# iomk4.net
KiCad netlist of a schematic drawn in EAGLE
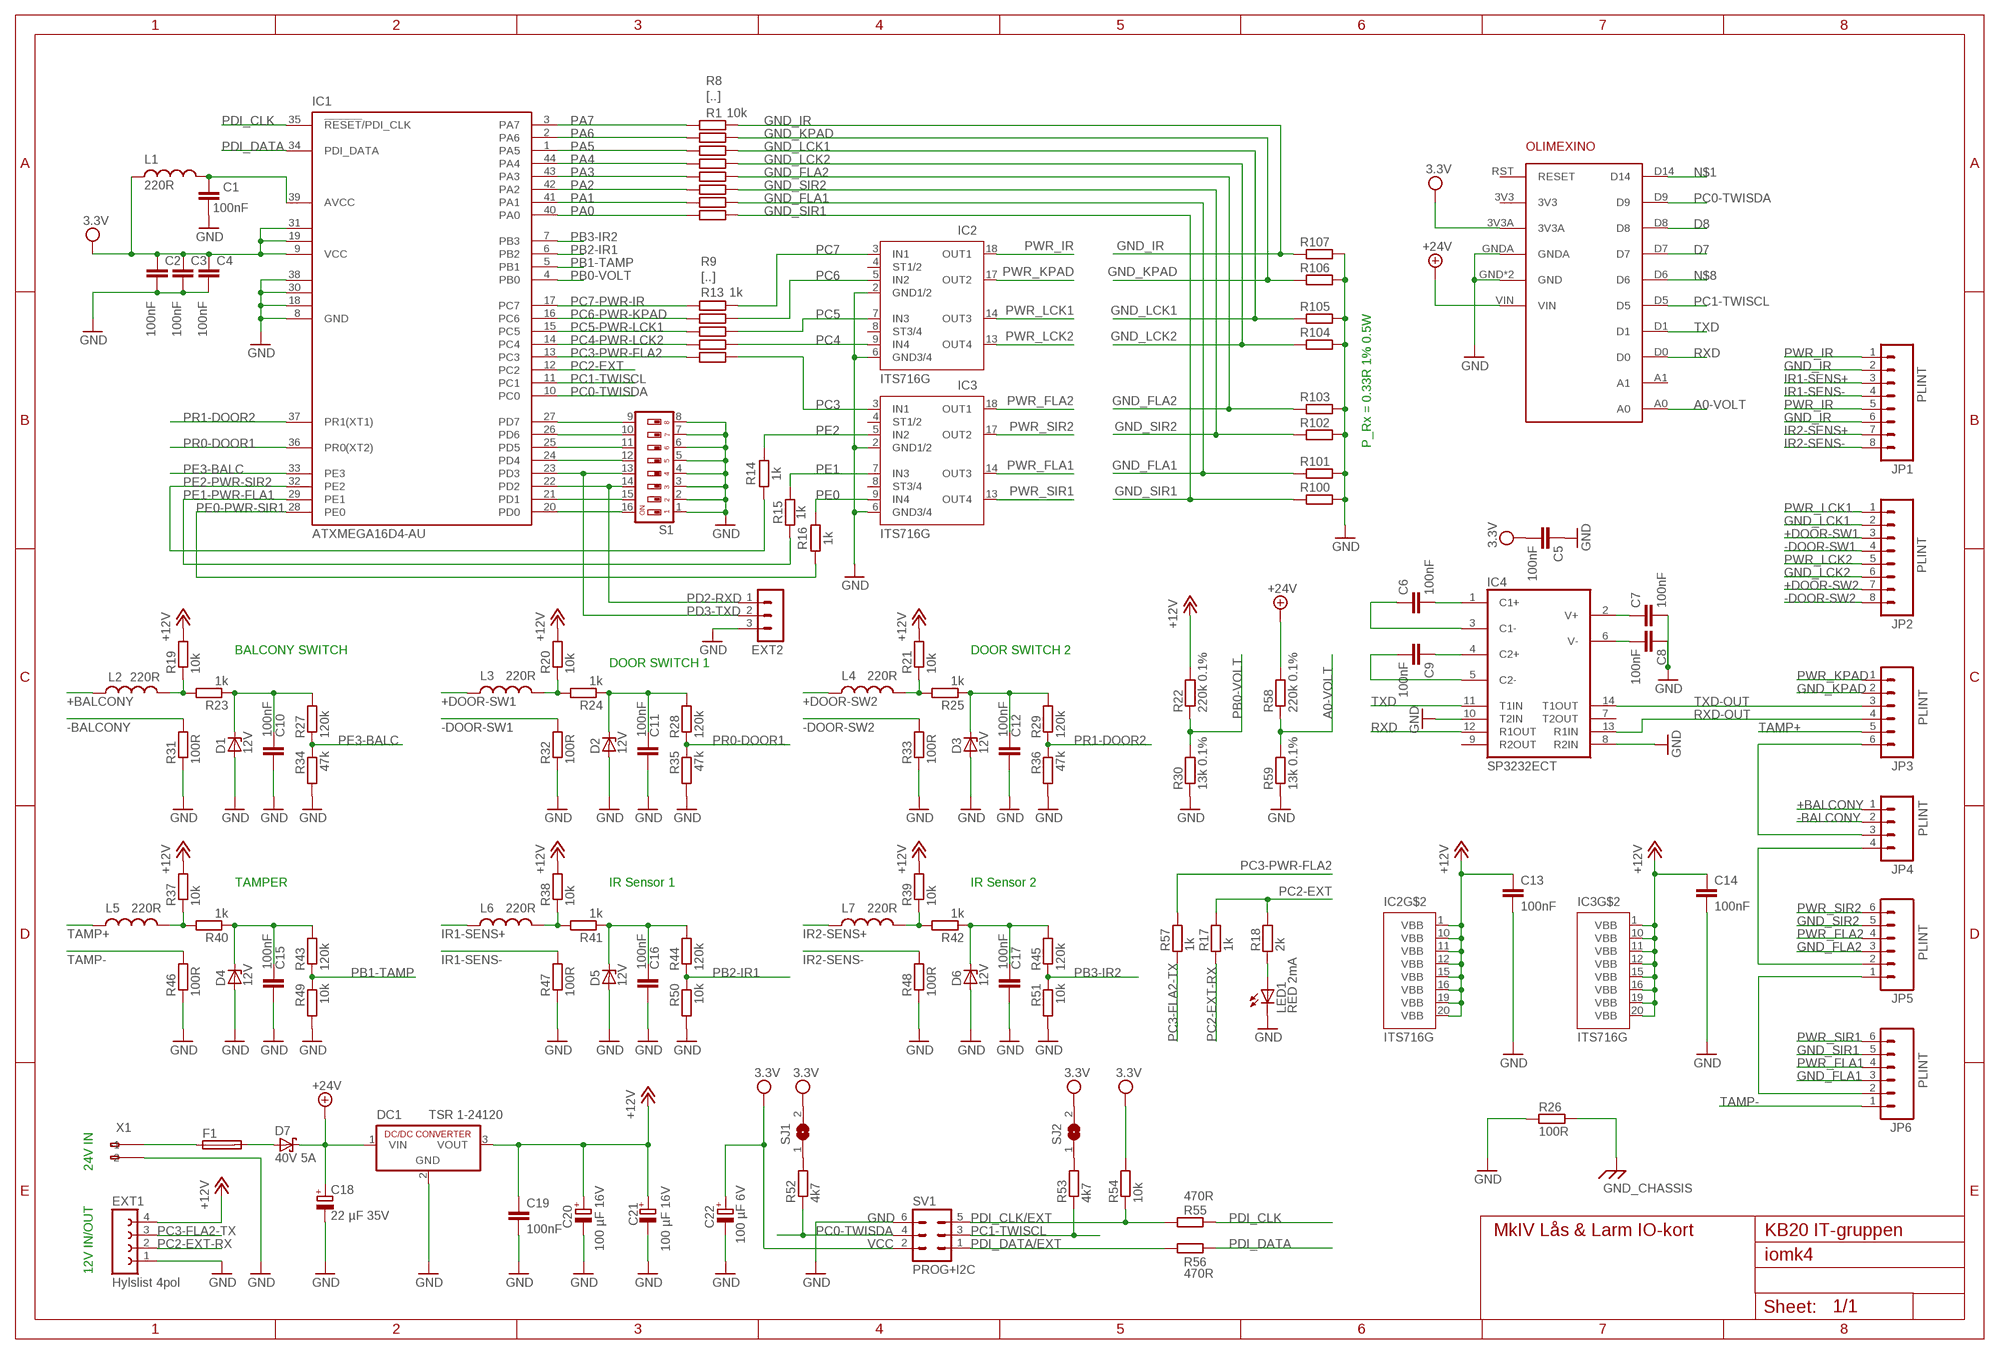
[diagram p0: schematic, sheet 1]

(export (version "E")
  (design (tool "Eeschema 10.0.6"))
  (components
    (comp (ref "C1")
      (value "100nF")
      (footprint "eagle-import:C0805")
      (libsource (lib "eagle-import") (part "CAPACITOR"))
    )
    (comp (ref "C2")
      (value "100nF")
      (footprint "eagle-import:C0805")
      (libsource (lib "eagle-import") (part "CAPACITOR"))
    )
    (comp (ref "C3")
      (value "100nF")
      (footprint "eagle-import:C0805")
      (libsource (lib "eagle-import") (part "CAPACITOR"))
    )
    (comp (ref "C4")
      (value "100nF")
      (footprint "eagle-import:C0805")
      (libsource (lib "eagle-import") (part "CAPACITOR"))
    )
    (comp (ref "C5")
      (value "100nF")
      (footprint "eagle-import:C0805")
      (libsource (lib "eagle-import") (part "CAPACITOR"))
    )
    (comp (ref "C6")
      (value "100nF")
      (footprint "eagle-import:C0805")
      (libsource (lib "eagle-import") (part "CAPACITOR"))
    )
    (comp (ref "C7")
      (value "100nF")
      (footprint "eagle-import:C0805")
      (libsource (lib "eagle-import") (part "CAPACITOR"))
    )
    (comp (ref "C8")
      (value "100nF")
      (footprint "eagle-import:C0805")
      (libsource (lib "eagle-import") (part "CAPACITOR"))
    )
    (comp (ref "C9")
      (value "100nF")
      (footprint "eagle-import:C0805")
      (libsource (lib "eagle-import") (part "CAPACITOR"))
    )
    (comp (ref "C10")
      (value "100nF")
      (footprint "eagle-import:C0805")
      (libsource (lib "eagle-import") (part "CAPACITOR"))
    )
    (comp (ref "C11")
      (value "100nF")
      (footprint "eagle-import:C0805")
      (libsource (lib "eagle-import") (part "CAPACITOR"))
    )
    (comp (ref "C12")
      (value "100nF")
      (footprint "eagle-import:C0805")
      (libsource (lib "eagle-import") (part "CAPACITOR"))
    )
    (comp (ref "C13")
      (value "100nF")
      (footprint "eagle-import:C0805")
      (libsource (lib "eagle-import") (part "CAPACITOR"))
    )
    (comp (ref "C14")
      (value "100nF")
      (footprint "eagle-import:C0805")
      (libsource (lib "eagle-import") (part "CAPACITOR"))
    )
    (comp (ref "C15")
      (value "100nF")
      (footprint "eagle-import:C0805")
      (libsource (lib "eagle-import") (part "CAPACITOR"))
    )
    (comp (ref "C16")
      (value "100nF")
      (footprint "eagle-import:C0805")
      (libsource (lib "eagle-import") (part "CAPACITOR"))
    )
    (comp (ref "C17")
      (value "100nF")
      (footprint "eagle-import:C0805")
      (libsource (lib "eagle-import") (part "CAPACITOR"))
    )
    (comp (ref "C18")
      (value "22 µF 35V")
      (footprint "eagle-import:D_7343-31R")
      (libsource (lib "eagle-import") (part "CPOL-EUD/7343-31R"))
    )
    (comp (ref "C19")
      (value "100nF")
      (footprint "eagle-import:C0805")
      (libsource (lib "eagle-import") (part "CAPACITOR"))
    )
    (comp (ref "C20")
      (value "100 µF 16V")
      (footprint "eagle-import:D_7343-31R")
      (libsource (lib "eagle-import") (part "CPOL-EUD/7343-31R"))
    )
    (comp (ref "C21")
      (value "100 µF 16V")
      (footprint "eagle-import:D_7343-31R")
      (libsource (lib "eagle-import") (part "CPOL-EUD/7343-31R"))
    )
    (comp (ref "C22")
      (value "100 µF 6V")
      (footprint "eagle-import:CT6032")
      (libsource (lib "eagle-import") (part "CPOL-EUCT6032"))
    )
    (comp (ref "D1")
      (value "12V")
      (footprint "eagle-import:SOD80C")
      (libsource (lib "eagle-import") (part "ZENER-DIODESOD80C"))
    )
    (comp (ref "D2")
      (value "12V")
      (footprint "eagle-import:SOD80C")
      (libsource (lib "eagle-import") (part "ZENER-DIODESOD80C"))
    )
    (comp (ref "D3")
      (value "12V")
      (footprint "eagle-import:SOD80C")
      (libsource (lib "eagle-import") (part "ZENER-DIODESOD80C"))
    )
    (comp (ref "D4")
      (value "12V")
      (footprint "eagle-import:SOD80C")
      (libsource (lib "eagle-import") (part "ZENER-DIODESOD80C"))
    )
    (comp (ref "D5")
      (value "12V")
      (footprint "eagle-import:SOD80C")
      (libsource (lib "eagle-import") (part "ZENER-DIODESOD80C"))
    )
    (comp (ref "D6")
      (value "12V")
      (footprint "eagle-import:SOD80C")
      (libsource (lib "eagle-import") (part "ZENER-DIODESOD80C"))
    )
    (comp (ref "D7")
      (value "40V 5A")
      (footprint "eagle-import:SMB")
      (libsource (lib "eagle-import") (part "SCHOTTKY-DIODESMD"))
    )
    (comp (ref "DC1")
      (value "TSR 1-24120")
      (footprint "eagle-import:SIP3")
      (libsource (lib "eagle-import") (part "R-78C-1.012"))
    )
    (comp (ref "EXT1")
      (value "Hylslist 4pol")
      (footprint "eagle-import:FE04")
      (libsource (lib "eagle-import") (part "FE04"))
    )
    (comp (ref "EXT2")
      (value "DEBUG PINS")
      (footprint "eagle-import:MA03")
      (libsource (lib "eagle-import") (part "MA03-1-"))
    )
    (comp (ref "F1")
      (value "Fuse Holder")
      (footprint "eagle-import:FTP_60")
      (libsource (lib "eagle-import") (part "FUSEFTP/60"))
    )
    (comp (ref "IC1")
      (value "ATXMEGA16D4-AU")
      (footprint "eagle-import:TQFP44")
      (fields
        (field (name "MF") "ATMEL")
        (field (name "MPN") "ATXMEGA16A4-AU")
        (field (name "OC_FARNELL") "1748552")
      )
      (libsource (lib "eagle-import") (part "XMEGA16A4A"))
    )
    (comp (ref "IC2")
      (value "ITS716G")
      (footprint "eagle-import:PG-DSO-20")
      (fields (field (name "ELFA") "71-017-02"))
      (libsource (lib "eagle-import") (part "BTS716G"))
    )
    (comp (ref "IC3")
      (value "ITS716G")
      (footprint "eagle-import:PG-DSO-20")
      (fields (field (name "ELFA") "71-017-02"))
      (libsource (lib "eagle-import") (part "BTS716G"))
    )
    (comp (ref "IC4")
      (value "SP3232ECT")
      (footprint "eagle-import:SO16L")
      (fields
        (field (name "MF") "MAXIM")
        (field (name "MPN") "MAX3232CWE+")
        (field (name "MF_1") "MAXIM INTEGRATED PRODUCTS")
        (field (name "MPN_1") "MAX3232CSE+")
      )
      (libsource (lib "eagle-import") (part "MAX3232WEC"))
    )
    (comp (ref "JP1")
      (value "PLINT")
      (footprint "eagle-import:FK-MPT-8-3,5")
      (libsource (lib "eagle-import") (part "FK-MPT-8-3.5"))
    )
    (comp (ref "JP2")
      (value "PLINT")
      (footprint "eagle-import:FK-MPT-8-3,5")
      (libsource (lib "eagle-import") (part "FK-MPT-8-3.5"))
    )
    (comp (ref "JP3")
      (value "PLINT")
      (footprint "eagle-import:FK-MPT-6-3,5")
      (libsource (lib "eagle-import") (part "FK-MPT-6-3.5"))
    )
    (comp (ref "JP4")
      (value "PLINT")
      (footprint "eagle-import:FK-MPT-4-3.5")
      (libsource (lib "eagle-import") (part "FK-MPT-4-3.5"))
    )
    (comp (ref "JP5")
      (value "PLINT")
      (footprint "eagle-import:FK-MPT-6-3,5")
      (libsource (lib "eagle-import") (part "FK-MPT-6-3.5"))
    )
    (comp (ref "JP6")
      (value "PLINT")
      (footprint "eagle-import:FK-MPT-6-3,5")
      (libsource (lib "eagle-import") (part "FK-MPT-6-3.5"))
    )
    (comp (ref "L1")
      (value "220R")
      (footprint "eagle-import:L0805")
      (libsource (lib "eagle-import") (part "FERRITE-BEADSL"))
    )
    (comp (ref "L2")
      (value "220R")
      (footprint "eagle-import:L0805")
      (libsource (lib "eagle-import") (part "FERRITE-BEADSL"))
    )
    (comp (ref "L3")
      (value "220R")
      (footprint "eagle-import:L0805")
      (libsource (lib "eagle-import") (part "FERRITE-BEADSL"))
    )
    (comp (ref "L4")
      (value "220R")
      (footprint "eagle-import:L0805")
      (libsource (lib "eagle-import") (part "FERRITE-BEADSL"))
    )
    (comp (ref "L5")
      (value "220R")
      (footprint "eagle-import:L0805")
      (libsource (lib "eagle-import") (part "FERRITE-BEADSL"))
    )
    (comp (ref "L6")
      (value "220R")
      (footprint "eagle-import:L0805")
      (libsource (lib "eagle-import") (part "FERRITE-BEADSL"))
    )
    (comp (ref "L7")
      (value "220R")
      (footprint "eagle-import:L0805")
      (libsource (lib "eagle-import") (part "FERRITE-BEADSL"))
    )
    (comp (ref "LED1")
      (value "RED 2mA")
      (footprint "eagle-import:SML0603")
      (libsource (lib "eagle-import") (part "LEDSML0603"))
    )
    (comp (ref "OLIMEXINO-STM1")
      (value "OLIMEXINO")
      (footprint "eagle-import:OLIMEXINO-STM32")
      (libsource (lib "eagle-import") (part "OLIMEXINO"))
    )
    (comp (ref "R1")
      (value "10k")
      (footprint "eagle-import:R0805")
      (libsource (lib "eagle-import") (part "RESISTORR0805"))
    )
    (comp (ref "R2")
      (value "10k")
      (footprint "eagle-import:R0805")
      (libsource (lib "eagle-import") (part "RESISTORR0805"))
    )
    (comp (ref "R3")
      (value "10k")
      (footprint "eagle-import:R0805")
      (libsource (lib "eagle-import") (part "RESISTORR0805"))
    )
    (comp (ref "R4")
      (value "10k")
      (footprint "eagle-import:R0805")
      (libsource (lib "eagle-import") (part "RESISTORR0805"))
    )
    (comp (ref "R5")
      (value "10k")
      (footprint "eagle-import:R0805")
      (libsource (lib "eagle-import") (part "RESISTORR0805"))
    )
    (comp (ref "R6")
      (value "10k")
      (footprint "eagle-import:R0805")
      (libsource (lib "eagle-import") (part "RESISTORR0805"))
    )
    (comp (ref "R7")
      (value "10k")
      (footprint "eagle-import:R0805")
      (libsource (lib "eagle-import") (part "RESISTORR0805"))
    )
    (comp (ref "R8")
      (value "10k")
      (footprint "eagle-import:R0805")
      (libsource (lib "eagle-import") (part "RESISTORR0805"))
    )
    (comp (ref "R9")
      (value "1k")
      (footprint "eagle-import:R0805")
      (libsource (lib "eagle-import") (part "RESISTORR0805"))
    )
    (comp (ref "R10")
      (value "1k")
      (footprint "eagle-import:R0805")
      (libsource (lib "eagle-import") (part "RESISTORR0805"))
    )
    (comp (ref "R11")
      (value "1k")
      (footprint "eagle-import:R0805")
      (libsource (lib "eagle-import") (part "RESISTORR0805"))
    )
    (comp (ref "R12")
      (value "1k")
      (footprint "eagle-import:R0805")
      (libsource (lib "eagle-import") (part "RESISTORR0805"))
    )
    (comp (ref "R13")
      (value "1k")
      (footprint "eagle-import:R0805")
      (libsource (lib "eagle-import") (part "RESISTORR0805"))
    )
    (comp (ref "R14")
      (value "1k")
      (footprint "eagle-import:R0805")
      (libsource (lib "eagle-import") (part "RESISTORR0805"))
    )
    (comp (ref "R15")
      (value "1k")
      (footprint "eagle-import:R0805")
      (libsource (lib "eagle-import") (part "RESISTORR0805"))
    )
    (comp (ref "R16")
      (value "1k")
      (footprint "eagle-import:R0805")
      (libsource (lib "eagle-import") (part "RESISTORR0805"))
    )
    (comp (ref "R17")
      (value "1k")
      (footprint "eagle-import:R0805")
      (libsource (lib "eagle-import") (part "RESISTORR0805"))
    )
    (comp (ref "R18")
      (value "2k")
      (footprint "eagle-import:R0805")
      (libsource (lib "eagle-import") (part "RESISTORR0805"))
    )
    (comp (ref "R19")
      (value "10k")
      (footprint "eagle-import:R0805")
      (libsource (lib "eagle-import") (part "RESISTORR0805"))
    )
    (comp (ref "R20")
      (value "10k")
      (footprint "eagle-import:R0805")
      (libsource (lib "eagle-import") (part "RESISTORR0805"))
    )
    (comp (ref "R21")
      (value "10k")
      (footprint "eagle-import:R0805")
      (libsource (lib "eagle-import") (part "RESISTORR0805"))
    )
    (comp (ref "R22")
      (value "220k 0.1%")
      (footprint "eagle-import:R0805")
      (libsource (lib "eagle-import") (part "RESISTORR0805"))
    )
    (comp (ref "R23")
      (value "1k")
      (footprint "eagle-import:R0805")
      (libsource (lib "eagle-import") (part "RESISTORR0805"))
    )
    (comp (ref "R24")
      (value "1k")
      (footprint "eagle-import:R0805")
      (libsource (lib "eagle-import") (part "RESISTORR0805"))
    )
    (comp (ref "R25")
      (value "1k")
      (footprint "eagle-import:R0805")
      (libsource (lib "eagle-import") (part "RESISTORR0805"))
    )
    (comp (ref "R26")
      (value "100R")
      (footprint "eagle-import:R0805")
      (libsource (lib "eagle-import") (part "RESISTORR0805"))
    )
    (comp (ref "R27")
      (value "120k")
      (footprint "eagle-import:R0805")
      (libsource (lib "eagle-import") (part "RESISTORR0805"))
    )
    (comp (ref "R28")
      (value "120k")
      (footprint "eagle-import:R0805")
      (libsource (lib "eagle-import") (part "RESISTORR0805"))
    )
    (comp (ref "R29")
      (value "120k")
      (footprint "eagle-import:R0805")
      (libsource (lib "eagle-import") (part "RESISTORR0805"))
    )
    (comp (ref "R30")
      (value "13k 0.1%")
      (footprint "eagle-import:R0805")
      (libsource (lib "eagle-import") (part "RESISTORR0805"))
    )
    (comp (ref "R31")
      (value "100R")
      (footprint "eagle-import:R0805")
      (libsource (lib "eagle-import") (part "RESISTORR0805"))
    )
    (comp (ref "R32")
      (value "100R")
      (footprint "eagle-import:R0805")
      (libsource (lib "eagle-import") (part "RESISTORR0805"))
    )
    (comp (ref "R33")
      (value "100R")
      (footprint "eagle-import:R0805")
      (libsource (lib "eagle-import") (part "RESISTORR0805"))
    )
    (comp (ref "R34")
      (value "47k")
      (footprint "eagle-import:R0805")
      (libsource (lib "eagle-import") (part "RESISTORR0805"))
    )
    (comp (ref "R35")
      (value "47k")
      (footprint "eagle-import:R0805")
      (libsource (lib "eagle-import") (part "RESISTORR0805"))
    )
    (comp (ref "R36")
      (value "47k")
      (footprint "eagle-import:R0805")
      (libsource (lib "eagle-import") (part "RESISTORR0805"))
    )
    (comp (ref "R37")
      (value "10k")
      (footprint "eagle-import:R0805")
      (libsource (lib "eagle-import") (part "RESISTORR0805"))
    )
    (comp (ref "R38")
      (value "10k")
      (footprint "eagle-import:R0805")
      (libsource (lib "eagle-import") (part "RESISTORR0805"))
    )
    (comp (ref "R39")
      (value "10k")
      (footprint "eagle-import:R0805")
      (libsource (lib "eagle-import") (part "RESISTORR0805"))
    )
    (comp (ref "R40")
      (value "1k")
      (footprint "eagle-import:R0805")
      (libsource (lib "eagle-import") (part "RESISTORR0805"))
    )
    (comp (ref "R41")
      (value "1k")
      (footprint "eagle-import:R0805")
      (libsource (lib "eagle-import") (part "RESISTORR0805"))
    )
    (comp (ref "R42")
      (value "1k")
      (footprint "eagle-import:R0805")
      (libsource (lib "eagle-import") (part "RESISTORR0805"))
    )
    (comp (ref "R43")
      (value "120k")
      (footprint "eagle-import:R0805")
      (libsource (lib "eagle-import") (part "RESISTORR0805"))
    )
    (comp (ref "R44")
      (value "120k")
      (footprint "eagle-import:R0805")
      (libsource (lib "eagle-import") (part "RESISTORR0805"))
    )
    (comp (ref "R45")
      (value "120k")
      (footprint "eagle-import:R0805")
      (libsource (lib "eagle-import") (part "RESISTORR0805"))
    )
    (comp (ref "R46")
      (value "100R")
      (footprint "eagle-import:R0805")
      (libsource (lib "eagle-import") (part "RESISTORR0805"))
    )
    (comp (ref "R47")
      (value "100R")
      (footprint "eagle-import:R0805")
      (libsource (lib "eagle-import") (part "RESISTORR0805"))
    )
    (comp (ref "R48")
      (value "100R")
      (footprint "eagle-import:R0805")
      (libsource (lib "eagle-import") (part "RESISTORR0805"))
    )
    (comp (ref "R49")
      (value "10k")
      (footprint "eagle-import:R0805")
      (libsource (lib "eagle-import") (part "RESISTORR0805"))
    )
    (comp (ref "R50")
      (value "10k")
      (footprint "eagle-import:R0805")
      (libsource (lib "eagle-import") (part "RESISTORR0805"))
    )
    (comp (ref "R51")
      (value "10k")
      (footprint "eagle-import:R0805")
      (libsource (lib "eagle-import") (part "RESISTORR0805"))
    )
    (comp (ref "R52")
      (value "4k7")
      (footprint "eagle-import:R0805")
      (libsource (lib "eagle-import") (part "RESISTORR0805"))
    )
    (comp (ref "R53")
      (value "4k7")
      (footprint "eagle-import:R0805")
      (libsource (lib "eagle-import") (part "RESISTORR0805"))
    )
    (comp (ref "R54")
      (value "10k")
      (footprint "eagle-import:R0805")
      (libsource (lib "eagle-import") (part "RESISTORR0805"))
    )
    (comp (ref "R55")
      (value "470R")
      (footprint "eagle-import:R0805")
      (libsource (lib "eagle-import") (part "RESISTORR0805"))
    )
    (comp (ref "R56")
      (value "470R")
      (footprint "eagle-import:R0805")
      (libsource (lib "eagle-import") (part "RESISTORR0805"))
    )
    (comp (ref "R57")
      (value "1k")
      (footprint "eagle-import:R0805")
      (libsource (lib "eagle-import") (part "RESISTORR0805"))
    )
    (comp (ref "R58")
      (value "220k 0.1%")
      (footprint "eagle-import:R0805")
      (libsource (lib "eagle-import") (part "RESISTORR0805"))
    )
    (comp (ref "R59")
      (value "13k 0.1%")
      (footprint "eagle-import:R0805")
      (libsource (lib "eagle-import") (part "RESISTORR0805"))
    )
    (comp (ref "R100")
      (value "0.33R")
      (footprint "eagle-import:R1210")
      (libsource (lib "eagle-import") (part "RESISTORR1210"))
    )
    (comp (ref "R101")
      (value "0.33R")
      (footprint "eagle-import:R1210")
      (libsource (lib "eagle-import") (part "RESISTORR1210"))
    )
    (comp (ref "R102")
      (value "0.33R")
      (footprint "eagle-import:R1210")
      (libsource (lib "eagle-import") (part "RESISTORR1210"))
    )
    (comp (ref "R103")
      (value "0.33R")
      (footprint "eagle-import:R1210")
      (libsource (lib "eagle-import") (part "RESISTORR1210"))
    )
    (comp (ref "R104")
      (value "0.33R")
      (footprint "eagle-import:R1210")
      (libsource (lib "eagle-import") (part "RESISTORR1210"))
    )
    (comp (ref "R105")
      (value "0.33R")
      (footprint "eagle-import:R1210")
      (libsource (lib "eagle-import") (part "RESISTORR1210"))
    )
    (comp (ref "R106")
      (value "0.33R")
      (footprint "eagle-import:R1210")
      (libsource (lib "eagle-import") (part "RESISTORR1210"))
    )
    (comp (ref "R107")
      (value "0.33R")
      (footprint "eagle-import:R1210")
      (libsource (lib "eagle-import") (part "RESISTORR1210"))
    )
    (comp (ref "S1")
      (value "DIP switches")
      (footprint "eagle-import:DIL08-SMD-MINI")
      (libsource (lib "eagle-import") (part "SWS008"))
    )
    (comp (ref "SJ1")
      (value "Solder jumper")
      (footprint "eagle-import:SJ")
      (libsource (lib "eagle-import") (part "SJ"))
    )
    (comp (ref "SJ2")
      (value "Solder jumper")
      (footprint "eagle-import:SJ")
      (libsource (lib "eagle-import") (part "SJ"))
    )
    (comp (ref "SV1")
      (value "PROG+I2C")
      (footprint "eagle-import:ML6L")
      (libsource (lib "eagle-import") (part "ML6L"))
    )
    (comp (ref "X1")
      (value "PLINT")
      (footprint "eagle-import:255-402-5")
      (libsource (lib "eagle-import") (part "255-402-5"))
    )
  )
  (nets
    (net (code "1") (name "+12V") (class "Default")
      (node (ref "C13") (pin "1") (pinfunction "1_1") (pintype "passive"))
      (node (ref "C14") (pin "1") (pinfunction "1_1") (pintype "passive"))
      (node (ref "C19") (pin "1") (pinfunction "1_1") (pintype "passive"))
      (node (ref "C20") (pin "+") (pinfunction "+_+") (pintype "passive"))
      (node (ref "C21") (pin "+") (pinfunction "+_+") (pintype "passive"))
      (node (ref "DC1") (pin "3") (pinfunction "VOUT_3") (pintype "passive"))
      (node (ref "EXT1") (pin "4") (pinfunction "4_4") (pintype "passive"))
      (node (ref "IC2") (pin "1") (pinfunction "VBB_1") (pintype "power_in"))
      (node (ref "IC2") (pin "10") (pinfunction "VBB_10") (pintype "power_in"))
      (node (ref "IC2") (pin "11") (pinfunction "VBB_11") (pintype "power_in"))
      (node (ref "IC2") (pin "12") (pinfunction "VBB_12") (pintype "power_in"))
      (node (ref "IC2") (pin "15") (pinfunction "VBB_15") (pintype "power_in"))
      (node (ref "IC2") (pin "16") (pinfunction "VBB_16") (pintype "power_in"))
      (node (ref "IC2") (pin "19") (pinfunction "VBB_19") (pintype "power_in"))
      (node (ref "IC2") (pin "20") (pinfunction "VBB_20") (pintype "power_in"))
      (node (ref "IC3") (pin "1") (pinfunction "VBB_1") (pintype "power_in"))
      (node (ref "IC3") (pin "10") (pinfunction "VBB_10") (pintype "power_in"))
      (node (ref "IC3") (pin "11") (pinfunction "VBB_11") (pintype "power_in"))
      (node (ref "IC3") (pin "12") (pinfunction "VBB_12") (pintype "power_in"))
      (node (ref "IC3") (pin "15") (pinfunction "VBB_15") (pintype "power_in"))
      (node (ref "IC3") (pin "16") (pinfunction "VBB_16") (pintype "power_in"))
      (node (ref "IC3") (pin "19") (pinfunction "VBB_19") (pintype "power_in"))
      (node (ref "IC3") (pin "20") (pinfunction "VBB_20") (pintype "power_in"))
      (node (ref "R19") (pin "2") (pinfunction "2_2") (pintype "passive"))
      (node (ref "R20") (pin "2") (pinfunction "2_2") (pintype "passive"))
      (node (ref "R21") (pin "2") (pinfunction "2_2") (pintype "passive"))
      (node (ref "R22") (pin "2") (pinfunction "2_2") (pintype "passive"))
      (node (ref "R37") (pin "2") (pinfunction "2_2") (pintype "passive"))
      (node (ref "R38") (pin "2") (pinfunction "2_2") (pintype "passive"))
      (node (ref "R39") (pin "2") (pinfunction "2_2") (pintype "passive"))
    )
    (net (code "2") (name "+24V") (class "Default")
      (node (ref "C18") (pin "+") (pinfunction "+_+") (pintype "passive"))
      (node (ref "D7") (pin "C") (pinfunction "C_C") (pintype "passive"))
      (node (ref "DC1") (pin "1") (pinfunction "VIN_1") (pintype "passive"))
      (node (ref "OLIMEXINO-STM1") (pin "VIN") (pinfunction "VIN_VIN") (pintype "bidirectional"))
      (node (ref "R58") (pin "2") (pinfunction "2_2") (pintype "passive"))
    )
    (net (code "3") (name "/+BALCONY") (class "Default")
      (node (ref "JP4") (pin "1") (pinfunction "1_1") (pintype "passive"))
      (node (ref "L2") (pin "1") (pinfunction "1_1") (pintype "passive"))
    )
    (net (code "4") (name "/+DOOR-SW1") (class "Default")
      (node (ref "JP2") (pin "3") (pinfunction "3_3") (pintype "passive"))
      (node (ref "L3") (pin "1") (pinfunction "1_1") (pintype "passive"))
    )
    (net (code "5") (name "/+DOOR-SW2") (class "Default")
      (node (ref "JP2") (pin "7") (pinfunction "7_7") (pintype "passive"))
      (node (ref "L4") (pin "1") (pinfunction "1_1") (pintype "passive"))
    )
    (net (code "6") (name "/-BALCONY") (class "Default")
      (node (ref "JP4") (pin "2") (pinfunction "2_2") (pintype "passive"))
      (node (ref "R31") (pin "2") (pinfunction "2_2") (pintype "passive"))
    )
    (net (code "7") (name "/-DOOR-SW1") (class "Default")
      (node (ref "JP2") (pin "4") (pinfunction "4_4") (pintype "passive"))
      (node (ref "R32") (pin "2") (pinfunction "2_2") (pintype "passive"))
    )
    (net (code "8") (name "/-DOOR-SW2") (class "Default")
      (node (ref "JP2") (pin "8") (pinfunction "8_8") (pintype "passive"))
      (node (ref "R33") (pin "2") (pinfunction "2_2") (pintype "passive"))
    )
    (net (code "9") (name "/A0-VOLT") (class "Default")
      (node (ref "OLIMEXINO-STM1") (pin "A0") (pinfunction "A0_A0") (pintype "bidirectional"))
      (node (ref "R58") (pin "1") (pinfunction "1_1") (pintype "passive"))
      (node (ref "R59") (pin "2") (pinfunction "2_2") (pintype "passive"))
    )
    (net (code "10") (name "/D7") (class "Default")
      (node (ref "OLIMEXINO-STM1") (pin "D7") (pinfunction "D7_D7") (pintype "bidirectional"))
    )
    (net (code "11") (name "/D8") (class "Default")
      (node (ref "OLIMEXINO-STM1") (pin "D8") (pinfunction "D8_D8") (pintype "bidirectional"))
    )
    (net (code "12") (name "/GND_FLA1") (class "Default")
      (node (ref "JP6") (pin "3") (pinfunction "3_3") (pintype "passive"))
      (node (ref "R101") (pin "1") (pinfunction "1_1") (pintype "passive"))
      (node (ref "R2") (pin "2") (pinfunction "2_2") (pintype "passive"))
    )
    (net (code "13") (name "/GND_FLA2") (class "Default")
      (node (ref "JP5") (pin "3") (pinfunction "3_3") (pintype "passive"))
      (node (ref "R103") (pin "1") (pinfunction "1_1") (pintype "passive"))
      (node (ref "R4") (pin "2") (pinfunction "2_2") (pintype "passive"))
    )
    (net (code "14") (name "/GND_IR") (class "Default")
      (node (ref "JP1") (pin "2") (pinfunction "2_2") (pintype "passive"))
      (node (ref "JP1") (pin "6") (pinfunction "6_6") (pintype "passive"))
      (node (ref "R107") (pin "1") (pinfunction "1_1") (pintype "passive"))
      (node (ref "R8") (pin "2") (pinfunction "2_2") (pintype "passive"))
    )
    (net (code "15") (name "/GND_KPAD") (class "Default")
      (node (ref "JP3") (pin "2") (pinfunction "2_2") (pintype "passive"))
      (node (ref "R106") (pin "1") (pinfunction "1_1") (pintype "passive"))
      (node (ref "R7") (pin "2") (pinfunction "2_2") (pintype "passive"))
    )
    (net (code "16") (name "/GND_LCK1") (class "Default")
      (node (ref "JP2") (pin "2") (pinfunction "2_2") (pintype "passive"))
      (node (ref "R105") (pin "1") (pinfunction "1_1") (pintype "passive"))
      (node (ref "R6") (pin "2") (pinfunction "2_2") (pintype "passive"))
    )
    (net (code "17") (name "/GND_LCK2") (class "Default")
      (node (ref "JP2") (pin "6") (pinfunction "6_6") (pintype "passive"))
      (node (ref "R104") (pin "1") (pinfunction "1_1") (pintype "passive"))
      (node (ref "R5") (pin "2") (pinfunction "2_2") (pintype "passive"))
    )
    (net (code "18") (name "/GND_SIR1") (class "Default")
      (node (ref "JP6") (pin "5") (pinfunction "5_5") (pintype "passive"))
      (node (ref "R1") (pin "2") (pinfunction "2_2") (pintype "passive"))
      (node (ref "R100") (pin "1") (pinfunction "1_1") (pintype "passive"))
    )
    (net (code "19") (name "/GND_SIR2") (class "Default")
      (node (ref "JP5") (pin "5") (pinfunction "5_5") (pintype "passive"))
      (node (ref "R102") (pin "1") (pinfunction "1_1") (pintype "passive"))
      (node (ref "R3") (pin "2") (pinfunction "2_2") (pintype "passive"))
    )
    (net (code "20") (name "/IR1-SENS+") (class "Default")
      (node (ref "JP1") (pin "3") (pinfunction "3_3") (pintype "passive"))
      (node (ref "L6") (pin "1") (pinfunction "1_1") (pintype "passive"))
    )
    (net (code "21") (name "/IR1-SENS-") (class "Default")
      (node (ref "JP1") (pin "4") (pinfunction "4_4") (pintype "passive"))
      (node (ref "R47") (pin "2") (pinfunction "2_2") (pintype "passive"))
    )
    (net (code "22") (name "/IR2-SENS+") (class "Default")
      (node (ref "JP1") (pin "7") (pinfunction "7_7") (pintype "passive"))
      (node (ref "L7") (pin "1") (pinfunction "1_1") (pintype "passive"))
    )
    (net (code "23") (name "/IR2-SENS-") (class "Default")
      (node (ref "JP1") (pin "8") (pinfunction "8_8") (pintype "passive"))
      (node (ref "R48") (pin "2") (pinfunction "2_2") (pintype "passive"))
    )
    (net (code "24") (name "/N$1") (class "Default")
      (node (ref "OLIMEXINO-STM1") (pin "D14") (pinfunction "D14_D14") (pintype "bidirectional"))
    )
    (net (code "25") (name "/N$8") (class "Default")
      (node (ref "OLIMEXINO-STM1") (pin "D6") (pinfunction "D6_D6") (pintype "bidirectional"))
    )
    (net (code "26") (name "/PA0") (class "Default")
      (node (ref "IC1") (pin "40") (pinfunction "PA0_40") (pintype "bidirectional"))
      (node (ref "R1") (pin "1") (pinfunction "1_1") (pintype "passive"))
    )
    (net (code "27") (name "/PA1") (class "Default")
      (node (ref "IC1") (pin "41") (pinfunction "PA1_41") (pintype "bidirectional"))
      (node (ref "R2") (pin "1") (pinfunction "1_1") (pintype "passive"))
    )
    (net (code "28") (name "/PA2") (class "Default")
      (node (ref "IC1") (pin "42") (pinfunction "PA2_42") (pintype "bidirectional"))
      (node (ref "R3") (pin "1") (pinfunction "1_1") (pintype "passive"))
    )
    (net (code "29") (name "/PA3") (class "Default")
      (node (ref "IC1") (pin "43") (pinfunction "PA3_43") (pintype "bidirectional"))
      (node (ref "R4") (pin "1") (pinfunction "1_1") (pintype "passive"))
    )
    (net (code "30") (name "/PA4") (class "Default")
      (node (ref "IC1") (pin "44") (pinfunction "PA4_44") (pintype "bidirectional"))
      (node (ref "R5") (pin "1") (pinfunction "1_1") (pintype "passive"))
    )
    (net (code "31") (name "/PA5") (class "Default")
      (node (ref "IC1") (pin "1") (pinfunction "PA5_1") (pintype "bidirectional"))
      (node (ref "R6") (pin "1") (pinfunction "1_1") (pintype "passive"))
    )
    (net (code "32") (name "/PA6") (class "Default")
      (node (ref "IC1") (pin "2") (pinfunction "PA6_2") (pintype "bidirectional"))
      (node (ref "R7") (pin "1") (pinfunction "1_1") (pintype "passive"))
    )
    (net (code "33") (name "/PA7") (class "Default")
      (node (ref "IC1") (pin "3") (pinfunction "PA7_3") (pintype "bidirectional"))
      (node (ref "R8") (pin "1") (pinfunction "1_1") (pintype "passive"))
    )
    (net (code "34") (name "/PB0-VOLT") (class "Default")
      (node (ref "IC1") (pin "4") (pinfunction "PB0_4") (pintype "bidirectional"))
      (node (ref "R22") (pin "1") (pinfunction "1_1") (pintype "passive"))
      (node (ref "R30") (pin "2") (pinfunction "2_2") (pintype "passive"))
    )
    (net (code "35") (name "/PB1-TAMP") (class "Default")
      (node (ref "IC1") (pin "5") (pinfunction "PB1_5") (pintype "bidirectional"))
      (node (ref "R43") (pin "1") (pinfunction "1_1") (pintype "passive"))
      (node (ref "R49") (pin "1") (pinfunction "1_1") (pintype "passive"))
    )
    (net (code "36") (name "/PB2-IR1") (class "Default")
      (node (ref "IC1") (pin "6") (pinfunction "PB2_6") (pintype "bidirectional"))
      (node (ref "R44") (pin "1") (pinfunction "1_1") (pintype "passive"))
      (node (ref "R50") (pin "1") (pinfunction "1_1") (pintype "passive"))
    )
    (net (code "37") (name "/PB3-IR2") (class "Default")
      (node (ref "IC1") (pin "7") (pinfunction "PB3_7") (pintype "bidirectional"))
      (node (ref "R45") (pin "1") (pinfunction "1_1") (pintype "passive"))
      (node (ref "R51") (pin "1") (pinfunction "1_1") (pintype "passive"))
    )
    (net (code "38") (name "/PC0-TWISDA") (class "Default")
      (node (ref "IC1") (pin "10") (pinfunction "PC0_10") (pintype "bidirectional"))
      (node (ref "OLIMEXINO-STM1") (pin "D9") (pinfunction "D9_D9") (pintype "bidirectional"))
      (node (ref "R52") (pin "1") (pinfunction "1_1") (pintype "passive"))
      (node (ref "SV1") (pin "4") (pinfunction "4_4") (pintype "passive"))
    )
    (net (code "39") (name "/PC1-TWISCL") (class "Default")
      (node (ref "IC1") (pin "11") (pinfunction "PC1_11") (pintype "bidirectional"))
      (node (ref "OLIMEXINO-STM1") (pin "D5") (pinfunction "D5_D5") (pintype "bidirectional"))
      (node (ref "R53") (pin "1") (pinfunction "1_1") (pintype "passive"))
      (node (ref "SV1") (pin "3") (pinfunction "3_3") (pintype "passive"))
    )
    (net (code "40") (name "/PC2-EXT") (class "Default")
      (node (ref "IC1") (pin "12") (pinfunction "PC2_12") (pintype "bidirectional"))
      (node (ref "R17") (pin "1") (pinfunction "1_1") (pintype "passive"))
      (node (ref "R18") (pin "1") (pinfunction "1_1") (pintype "passive"))
    )
    (net (code "41") (name "/PC2-EXT-RX") (class "Default")
      (node (ref "EXT1") (pin "2") (pinfunction "2_2") (pintype "passive"))
      (node (ref "R17") (pin "2") (pinfunction "2_2") (pintype "passive"))
    )
    (net (code "42") (name "/PC3") (class "Default")
      (node (ref "IC3") (pin "3") (pinfunction "IN1_3") (pintype "input"))
      (node (ref "R13") (pin "1") (pinfunction "1_1") (pintype "passive"))
    )
    (net (code "43") (name "/PC3-FLA2-TX") (class "Default")
      (node (ref "EXT1") (pin "3") (pinfunction "3_3") (pintype "passive"))
      (node (ref "R57") (pin "1") (pinfunction "1_1") (pintype "passive"))
    )
    (net (code "44") (name "/PC3-PWR-FLA2") (class "Default")
      (node (ref "IC1") (pin "13") (pinfunction "PC3_13") (pintype "bidirectional"))
      (node (ref "R13") (pin "2") (pinfunction "2_2") (pintype "passive"))
      (node (ref "R57") (pin "2") (pinfunction "2_2") (pintype "passive"))
    )
    (net (code "45") (name "/PC4") (class "Default")
      (node (ref "IC2") (pin "9") (pinfunction "IN4_9") (pintype "input"))
      (node (ref "R12") (pin "1") (pinfunction "1_1") (pintype "passive"))
    )
    (net (code "46") (name "/PC4-PWR-LCK2") (class "Default")
      (node (ref "IC1") (pin "14") (pinfunction "PC4_14") (pintype "bidirectional"))
      (node (ref "R12") (pin "2") (pinfunction "2_2") (pintype "passive"))
    )
    (net (code "47") (name "/PC5") (class "Default")
      (node (ref "IC2") (pin "7") (pinfunction "IN3_7") (pintype "input"))
      (node (ref "R11") (pin "1") (pinfunction "1_1") (pintype "passive"))
    )
    (net (code "48") (name "/PC5-PWR-LCK1") (class "Default")
      (node (ref "IC1") (pin "15") (pinfunction "PC5_15") (pintype "bidirectional"))
      (node (ref "R11") (pin "2") (pinfunction "2_2") (pintype "passive"))
    )
    (net (code "49") (name "/PC6") (class "Default")
      (node (ref "IC2") (pin "5") (pinfunction "IN2_5") (pintype "input"))
      (node (ref "R10") (pin "1") (pinfunction "1_1") (pintype "passive"))
    )
    (net (code "50") (name "/PC6-PWR-KPAD") (class "Default")
      (node (ref "IC1") (pin "16") (pinfunction "PC6_16") (pintype "bidirectional"))
      (node (ref "R10") (pin "2") (pinfunction "2_2") (pintype "passive"))
    )
    (net (code "51") (name "/PC7") (class "Default")
      (node (ref "IC2") (pin "3") (pinfunction "IN1_3") (pintype "input"))
      (node (ref "R9") (pin "1") (pinfunction "1_1") (pintype "passive"))
    )
    (net (code "52") (name "/PC7-PWR-IR") (class "Default")
      (node (ref "IC1") (pin "17") (pinfunction "PC7_17") (pintype "bidirectional"))
      (node (ref "R9") (pin "2") (pinfunction "2_2") (pintype "passive"))
    )
    (net (code "53") (name "/PD2-RXD") (class "Default")
      (node (ref "EXT2") (pin "1") (pinfunction "1_1") (pintype "passive"))
      (node (ref "IC1") (pin "22") (pinfunction "PD2_22") (pintype "bidirectional"))
      (node (ref "S1") (pin "14") (pinfunction "14_14") (pintype "passive"))
    )
    (net (code "54") (name "/PD3-TXD") (class "Default")
      (node (ref "EXT2") (pin "2") (pinfunction "2_2") (pintype "passive"))
      (node (ref "IC1") (pin "23") (pinfunction "PD3_23") (pintype "bidirectional"))
      (node (ref "S1") (pin "13") (pinfunction "13_13") (pintype "passive"))
    )
    (net (code "55") (name "/PDI_CLK") (class "Default")
      (node (ref "IC1") (pin "35") (pinfunction "~{RESET}/PDI_CLK_35") (pintype "bidirectional"))
      (node (ref "R55") (pin "1") (pinfunction "1_1") (pintype "passive"))
    )
    (net (code "56") (name "/PDI_CLK{slash}EXT") (class "Default")
      (node (ref "R54") (pin "1") (pinfunction "1_1") (pintype "passive"))
      (node (ref "R55") (pin "2") (pinfunction "2_2") (pintype "passive"))
      (node (ref "SV1") (pin "5") (pinfunction "5_5") (pintype "passive"))
    )
    (net (code "57") (name "/PDI_DATA") (class "Default")
      (node (ref "IC1") (pin "34") (pinfunction "PDI_DATA_34") (pintype "bidirectional"))
      (node (ref "R56") (pin "1") (pinfunction "1_1") (pintype "passive"))
    )
    (net (code "58") (name "/PDI_DATA{slash}EXT") (class "Default")
      (node (ref "R56") (pin "2") (pinfunction "2_2") (pintype "passive"))
      (node (ref "SV1") (pin "1") (pinfunction "1_1") (pintype "passive"))
    )
    (net (code "59") (name "/PE0") (class "Default")
      (node (ref "IC3") (pin "9") (pinfunction "IN4_9") (pintype "input"))
      (node (ref "R16") (pin "1") (pinfunction "1_1") (pintype "passive"))
    )
    (net (code "60") (name "/PE0-PWR-SIR1") (class "Default")
      (node (ref "IC1") (pin "28") (pinfunction "PE0_28") (pintype "bidirectional"))
      (node (ref "R16") (pin "2") (pinfunction "2_2") (pintype "passive"))
    )
    (net (code "61") (name "/PE1") (class "Default")
      (node (ref "IC3") (pin "7") (pinfunction "IN3_7") (pintype "input"))
      (node (ref "R15") (pin "1") (pinfunction "1_1") (pintype "passive"))
    )
    (net (code "62") (name "/PE1-PWR-FLA1") (class "Default")
      (node (ref "IC1") (pin "29") (pinfunction "PE1_29") (pintype "bidirectional"))
      (node (ref "R15") (pin "2") (pinfunction "2_2") (pintype "passive"))
    )
    (net (code "63") (name "/PE2") (class "Default")
      (node (ref "IC3") (pin "5") (pinfunction "IN2_5") (pintype "input"))
      (node (ref "R14") (pin "1") (pinfunction "1_1") (pintype "passive"))
    )
    (net (code "64") (name "/PE2-PWR-SIR2") (class "Default")
      (node (ref "IC1") (pin "32") (pinfunction "PE2_32") (pintype "bidirectional"))
      (node (ref "R14") (pin "2") (pinfunction "2_2") (pintype "passive"))
    )
    (net (code "65") (name "/PE3-BALC") (class "Default")
      (node (ref "IC1") (pin "33") (pinfunction "PE3_33") (pintype "bidirectional"))
      (node (ref "R27") (pin "1") (pinfunction "1_1") (pintype "passive"))
      (node (ref "R34") (pin "1") (pinfunction "1_1") (pintype "passive"))
    )
    (net (code "66") (name "/PR0-DOOR1") (class "Default")
      (node (ref "IC1") (pin "36") (pinfunction "PR0(XT2)_36") (pintype "bidirectional"))
      (node (ref "R28") (pin "1") (pinfunction "1_1") (pintype "passive"))
      (node (ref "R35") (pin "1") (pinfunction "1_1") (pintype "passive"))
    )
    (net (code "67") (name "/PR1-DOOR2") (class "Default")
      (node (ref "IC1") (pin "37") (pinfunction "PR1(XT1)_37") (pintype "bidirectional"))
      (node (ref "R29") (pin "1") (pinfunction "1_1") (pintype "passive"))
      (node (ref "R36") (pin "1") (pinfunction "1_1") (pintype "passive"))
    )
    (net (code "68") (name "/PWR_FLA1") (class "Default")
      (node (ref "IC3") (pin "14") (pinfunction "OUT3_14") (pintype "output"))
      (node (ref "JP6") (pin "4") (pinfunction "4_4") (pintype "passive"))
    )
    (net (code "69") (name "/PWR_FLA2") (class "Default")
      (node (ref "IC3") (pin "18") (pinfunction "OUT1_18") (pintype "output"))
      (node (ref "JP5") (pin "4") (pinfunction "4_4") (pintype "passive"))
    )
    (net (code "70") (name "/PWR_IR") (class "Default")
      (node (ref "IC2") (pin "18") (pinfunction "OUT1_18") (pintype "output"))
      (node (ref "JP1") (pin "1") (pinfunction "1_1") (pintype "passive"))
      (node (ref "JP1") (pin "5") (pinfunction "5_5") (pintype "passive"))
    )
    (net (code "71") (name "/PWR_KPAD") (class "Default")
      (node (ref "IC2") (pin "17") (pinfunction "OUT2_17") (pintype "output"))
      (node (ref "JP3") (pin "1") (pinfunction "1_1") (pintype "passive"))
    )
    (net (code "72") (name "/PWR_LCK1") (class "Default")
      (node (ref "IC2") (pin "14") (pinfunction "OUT3_14") (pintype "output"))
      (node (ref "JP2") (pin "1") (pinfunction "1_1") (pintype "passive"))
    )
    (net (code "73") (name "/PWR_LCK2") (class "Default")
      (node (ref "IC2") (pin "13") (pinfunction "OUT4_13") (pintype "output"))
      (node (ref "JP2") (pin "5") (pinfunction "5_5") (pintype "passive"))
    )
    (net (code "74") (name "/PWR_SIR1") (class "Default")
      (node (ref "IC3") (pin "13") (pinfunction "OUT4_13") (pintype "output"))
      (node (ref "JP6") (pin "6") (pinfunction "6_6") (pintype "passive"))
    )
    (net (code "75") (name "/PWR_SIR2") (class "Default")
      (node (ref "IC3") (pin "17") (pinfunction "OUT2_17") (pintype "output"))
      (node (ref "JP5") (pin "6") (pinfunction "6_6") (pintype "passive"))
    )
    (net (code "76") (name "/RXD") (class "Default")
      (node (ref "IC4") (pin "12") (pinfunction "R1OUT_12") (pintype "output"))
      (node (ref "OLIMEXINO-STM1") (pin "D0") (pinfunction "D0_D0") (pintype "bidirectional"))
    )
    (net (code "77") (name "/RXD-OUT") (class "Default")
      (node (ref "IC4") (pin "13") (pinfunction "R1IN_13") (pintype "input"))
      (node (ref "JP3") (pin "4") (pinfunction "4_4") (pintype "passive"))
    )
    (net (code "78") (name "/TAMP+") (class "Default")
      (node (ref "JP3") (pin "5") (pinfunction "5_5") (pintype "passive"))
      (node (ref "L5") (pin "1") (pinfunction "1_1") (pintype "passive"))
    )
    (net (code "79") (name "/TAMP-") (class "Default")
      (node (ref "JP6") (pin "1") (pinfunction "1_1") (pintype "passive"))
      (node (ref "R46") (pin "2") (pinfunction "2_2") (pintype "passive"))
    )
    (net (code "80") (name "/TXD") (class "Default")
      (node (ref "IC4") (pin "11") (pinfunction "T1IN_11") (pintype "input"))
      (node (ref "OLIMEXINO-STM1") (pin "D1") (pinfunction "D1_D1") (pintype "bidirectional"))
    )
    (net (code "81") (name "/TXD-OUT") (class "Default")
      (node (ref "IC4") (pin "14") (pinfunction "T1OUT_14") (pintype "output"))
      (node (ref "JP3") (pin "3") (pinfunction "3_3") (pintype "passive"))
    )
    (net (code "82") (name "3.3V") (class "Default")
      (node (ref "C2") (pin "1") (pinfunction "1_1") (pintype "passive"))
      (node (ref "C22") (pin "+") (pinfunction "+_+") (pintype "passive"))
      (node (ref "C3") (pin "1") (pinfunction "1_1") (pintype "passive"))
      (node (ref "C4") (pin "1") (pinfunction "1_1") (pintype "passive"))
      (node (ref "C5") (pin "2") (pinfunction "2_2") (pintype "passive"))
      (node (ref "IC1") (pin "19") (pinfunction "VCC1_19") (pintype "power_in"))
      (node (ref "IC1") (pin "31") (pinfunction "VCC2_31") (pintype "power_in"))
      (node (ref "IC1") (pin "9") (pinfunction "VCC_9") (pintype "power_in"))
      (node (ref "L1") (pin "1") (pinfunction "1_1") (pintype "passive"))
      (node (ref "OLIMEXINO-STM1") (pin "3V3A") (pinfunction "3V3A_3V3A") (pintype "bidirectional"))
      (node (ref "R54") (pin "2") (pinfunction "2_2") (pintype "passive"))
      (node (ref "SJ1") (pin "2") (pinfunction "2_2") (pintype "passive"))
      (node (ref "SJ2") (pin "2") (pinfunction "2_2") (pintype "passive"))
      (node (ref "SV1") (pin "2") (pinfunction "2_2") (pintype "passive"))
    )
    (net (code "83") (name "GND") (class "Default")
      (node (ref "C1") (pin "2") (pinfunction "2_2") (pintype "passive"))
      (node (ref "C10") (pin "2") (pinfunction "2_2") (pintype "passive"))
      (node (ref "C11") (pin "2") (pinfunction "2_2") (pintype "passive"))
      (node (ref "C12") (pin "2") (pinfunction "2_2") (pintype "passive"))
      (node (ref "C13") (pin "2") (pinfunction "2_2") (pintype "passive"))
      (node (ref "C14") (pin "2") (pinfunction "2_2") (pintype "passive"))
      (node (ref "C15") (pin "2") (pinfunction "2_2") (pintype "passive"))
      (node (ref "C16") (pin "2") (pinfunction "2_2") (pintype "passive"))
      (node (ref "C17") (pin "2") (pinfunction "2_2") (pintype "passive"))
      (node (ref "C18") (pin "-") (pinfunction "-_-") (pintype "passive"))
      (node (ref "C19") (pin "2") (pinfunction "2_2") (pintype "passive"))
      (node (ref "C2") (pin "2") (pinfunction "2_2") (pintype "passive"))
      (node (ref "C20") (pin "-") (pinfunction "-_-") (pintype "passive"))
      (node (ref "C21") (pin "-") (pinfunction "-_-") (pintype "passive"))
      (node (ref "C22") (pin "-") (pinfunction "-_-") (pintype "passive"))
      (node (ref "C3") (pin "2") (pinfunction "2_2") (pintype "passive"))
      (node (ref "C4") (pin "2") (pinfunction "2_2") (pintype "passive"))
      (node (ref "C5") (pin "1") (pinfunction "1_1") (pintype "passive"))
      (node (ref "C7") (pin "2") (pinfunction "2_2") (pintype "passive"))
      (node (ref "C8") (pin "1") (pinfunction "1_1") (pintype "passive"))
      (node (ref "D1") (pin "A") (pinfunction "A_A") (pintype "passive"))
      (node (ref "D2") (pin "A") (pinfunction "A_A") (pintype "passive"))
      (node (ref "D3") (pin "A") (pinfunction "A_A") (pintype "passive"))
      (node (ref "D4") (pin "A") (pinfunction "A_A") (pintype "passive"))
      (node (ref "D5") (pin "A") (pinfunction "A_A") (pintype "passive"))
      (node (ref "D6") (pin "A") (pinfunction "A_A") (pintype "passive"))
      (node (ref "DC1") (pin "2") (pinfunction "GND_2") (pintype "passive"))
      (node (ref "EXT1") (pin "1") (pinfunction "1_1") (pintype "passive"))
      (node (ref "EXT2") (pin "3") (pinfunction "3_3") (pintype "passive"))
      (node (ref "IC1") (pin "18") (pinfunction "GND1_18") (pintype "power_in"))
      (node (ref "IC1") (pin "30") (pinfunction "GND2_30") (pintype "power_in"))
      (node (ref "IC1") (pin "38") (pinfunction "GND3_38") (pintype "power_in"))
      (node (ref "IC1") (pin "8") (pinfunction "GND_8") (pintype "power_in"))
      (node (ref "IC2") (pin "2") (pinfunction "GND1/2_2") (pintype "input"))
      (node (ref "IC2") (pin "6") (pinfunction "GND3/4_6") (pintype "input"))
      (node (ref "IC3") (pin "2") (pinfunction "GND1/2_2") (pintype "input"))
      (node (ref "IC3") (pin "6") (pinfunction "GND3/4_6") (pintype "input"))
      (node (ref "IC4") (pin "10") (pinfunction "T2IN_10") (pintype "input"))
      (node (ref "IC4") (pin "8") (pinfunction "R2IN_8") (pintype "input"))
      (node (ref "LED1") (pin "C") (pinfunction "C_C") (pintype "passive"))
      (node (ref "OLIMEXINO-STM1") (pin "GND") (pinfunction "GND_GND") (pintype "bidirectional"))
      (node (ref "OLIMEXINO-STM1") (pin "GND2") (pinfunction "GND_GND2") (pintype "bidirectional"))
      (node (ref "OLIMEXINO-STM1") (pin "GNDA") (pinfunction "GNDA_GNDA") (pintype "bidirectional"))
      (node (ref "R100") (pin "2") (pinfunction "2_2") (pintype "passive"))
      (node (ref "R101") (pin "2") (pinfunction "2_2") (pintype "passive"))
      (node (ref "R102") (pin "2") (pinfunction "2_2") (pintype "passive"))
      (node (ref "R103") (pin "2") (pinfunction "2_2") (pintype "passive"))
      (node (ref "R104") (pin "2") (pinfunction "2_2") (pintype "passive"))
      (node (ref "R105") (pin "2") (pinfunction "2_2") (pintype "passive"))
      (node (ref "R106") (pin "2") (pinfunction "2_2") (pintype "passive"))
      (node (ref "R107") (pin "2") (pinfunction "2_2") (pintype "passive"))
      (node (ref "R26") (pin "2") (pinfunction "2_2") (pintype "passive"))
      (node (ref "R30") (pin "1") (pinfunction "1_1") (pintype "passive"))
      (node (ref "R31") (pin "1") (pinfunction "1_1") (pintype "passive"))
      (node (ref "R32") (pin "1") (pinfunction "1_1") (pintype "passive"))
      (node (ref "R33") (pin "1") (pinfunction "1_1") (pintype "passive"))
      (node (ref "R34") (pin "2") (pinfunction "2_2") (pintype "passive"))
      (node (ref "R35") (pin "2") (pinfunction "2_2") (pintype "passive"))
      (node (ref "R36") (pin "2") (pinfunction "2_2") (pintype "passive"))
      (node (ref "R46") (pin "1") (pinfunction "1_1") (pintype "passive"))
      (node (ref "R47") (pin "1") (pinfunction "1_1") (pintype "passive"))
      (node (ref "R48") (pin "1") (pinfunction "1_1") (pintype "passive"))
      (node (ref "R49") (pin "2") (pinfunction "2_2") (pintype "passive"))
      (node (ref "R50") (pin "2") (pinfunction "2_2") (pintype "passive"))
      (node (ref "R51") (pin "2") (pinfunction "2_2") (pintype "passive"))
      (node (ref "R59") (pin "1") (pinfunction "1_1") (pintype "passive"))
      (node (ref "S1") (pin "1") (pinfunction "1_1") (pintype "passive"))
      (node (ref "S1") (pin "2") (pinfunction "2_2") (pintype "passive"))
      (node (ref "S1") (pin "3") (pinfunction "3_3") (pintype "passive"))
      (node (ref "S1") (pin "4") (pinfunction "4_4") (pintype "passive"))
      (node (ref "S1") (pin "5") (pinfunction "5_5") (pintype "passive"))
      (node (ref "S1") (pin "6") (pinfunction "6_6") (pintype "passive"))
      (node (ref "S1") (pin "7") (pinfunction "7_7") (pintype "passive"))
      (node (ref "S1") (pin "8") (pinfunction "8_8") (pintype "passive"))
      (node (ref "SV1") (pin "6") (pinfunction "6_6") (pintype "passive"))
      (node (ref "X1") (pin "A2") (pinfunction "-2_A2") (pintype "passive"))
    )
    (net (code "84") (name "GND_CHASSIS") (class "Default")
      (node (ref "R26") (pin "1") (pinfunction "1_1") (pintype "passive"))
    )
    (net (code "85") (name "Net-(C10-Pad1)") (class "Default")
      (node (ref "C10") (pin "1") (pinfunction "1_1") (pintype "passive"))
      (node (ref "D1") (pin "C") (pinfunction "C_C") (pintype "passive"))
      (node (ref "R23") (pin "1") (pinfunction "1_1") (pintype "passive"))
      (node (ref "R27") (pin "2") (pinfunction "2_2") (pintype "passive"))
    )
    (net (code "86") (name "Net-(C11-Pad1)") (class "Default")
      (node (ref "C11") (pin "1") (pinfunction "1_1") (pintype "passive"))
      (node (ref "D2") (pin "C") (pinfunction "C_C") (pintype "passive"))
      (node (ref "R24") (pin "1") (pinfunction "1_1") (pintype "passive"))
      (node (ref "R28") (pin "2") (pinfunction "2_2") (pintype "passive"))
    )
    (net (code "87") (name "Net-(C12-Pad1)") (class "Default")
      (node (ref "C12") (pin "1") (pinfunction "1_1") (pintype "passive"))
      (node (ref "D3") (pin "C") (pinfunction "C_C") (pintype "passive"))
      (node (ref "R25") (pin "1") (pinfunction "1_1") (pintype "passive"))
      (node (ref "R29") (pin "2") (pinfunction "2_2") (pintype "passive"))
    )
    (net (code "88") (name "Net-(C15-Pad1)") (class "Default")
      (node (ref "C15") (pin "1") (pinfunction "1_1") (pintype "passive"))
      (node (ref "D4") (pin "C") (pinfunction "C_C") (pintype "passive"))
      (node (ref "R40") (pin "1") (pinfunction "1_1") (pintype "passive"))
      (node (ref "R43") (pin "2") (pinfunction "2_2") (pintype "passive"))
    )
    (net (code "89") (name "Net-(C16-Pad1)") (class "Default")
      (node (ref "C16") (pin "1") (pinfunction "1_1") (pintype "passive"))
      (node (ref "D5") (pin "C") (pinfunction "C_C") (pintype "passive"))
      (node (ref "R41") (pin "1") (pinfunction "1_1") (pintype "passive"))
      (node (ref "R44") (pin "2") (pinfunction "2_2") (pintype "passive"))
    )
    (net (code "90") (name "Net-(C17-Pad1)") (class "Default")
      (node (ref "C17") (pin "1") (pinfunction "1_1") (pintype "passive"))
      (node (ref "D6") (pin "C") (pinfunction "C_C") (pintype "passive"))
      (node (ref "R42") (pin "1") (pinfunction "1_1") (pintype "passive"))
      (node (ref "R45") (pin "2") (pinfunction "2_2") (pintype "passive"))
    )
    (net (code "91") (name "Net-(D7-PadA)") (class "Default")
      (node (ref "D7") (pin "A") (pinfunction "A_A") (pintype "passive"))
      (node (ref "F1") (pin "2") (pinfunction "2_2") (pintype "passive"))
    )
    (net (code "92") (name "Net-(IC1-AVCC)") (class "Default")
      (node (ref "C1") (pin "1") (pinfunction "1_1") (pintype "passive"))
      (node (ref "IC1") (pin "39") (pinfunction "AVCC_39") (pintype "power_in"))
      (node (ref "L1") (pin "2") (pinfunction "2_2") (pintype "passive"))
    )
    (net (code "93") (name "Net-(IC1-PD0)") (class "Default")
      (node (ref "IC1") (pin "20") (pinfunction "PD0_20") (pintype "bidirectional"))
      (node (ref "S1") (pin "16") (pinfunction "16_16") (pintype "passive"))
    )
    (net (code "94") (name "Net-(IC1-PD1)") (class "Default")
      (node (ref "IC1") (pin "21") (pinfunction "PD1_21") (pintype "bidirectional"))
      (node (ref "S1") (pin "15") (pinfunction "15_15") (pintype "passive"))
    )
    (net (code "95") (name "Net-(IC1-PD4)") (class "Default")
      (node (ref "IC1") (pin "24") (pinfunction "PD4_24") (pintype "bidirectional"))
      (node (ref "S1") (pin "12") (pinfunction "12_12") (pintype "passive"))
    )
    (net (code "96") (name "Net-(IC1-PD5)") (class "Default")
      (node (ref "IC1") (pin "25") (pinfunction "PD5_25") (pintype "bidirectional"))
      (node (ref "S1") (pin "11") (pinfunction "11_11") (pintype "passive"))
    )
    (net (code "97") (name "Net-(IC1-PD6)") (class "Default")
      (node (ref "IC1") (pin "26") (pinfunction "PD6_26") (pintype "bidirectional"))
      (node (ref "S1") (pin "10") (pinfunction "10_10") (pintype "passive"))
    )
    (net (code "98") (name "Net-(IC1-PD7)") (class "Default")
      (node (ref "IC1") (pin "27") (pinfunction "PD7_27") (pintype "bidirectional"))
      (node (ref "S1") (pin "9") (pinfunction "9_9") (pintype "passive"))
    )
    (net (code "99") (name "Net-(IC4A-C1+)") (class "Default")
      (node (ref "C6") (pin "2") (pinfunction "2_2") (pintype "passive"))
      (node (ref "IC4") (pin "1") (pinfunction "C1+_1") (pintype "bidirectional"))
    )
    (net (code "100") (name "Net-(IC4A-C1-)") (class "Default")
      (node (ref "C6") (pin "1") (pinfunction "1_1") (pintype "passive"))
      (node (ref "IC4") (pin "3") (pinfunction "C1-_3") (pintype "bidirectional"))
    )
    (net (code "101") (name "Net-(IC4A-C2+)") (class "Default")
      (node (ref "C9") (pin "1") (pinfunction "1_1") (pintype "passive"))
      (node (ref "IC4") (pin "4") (pinfunction "C2+_4") (pintype "bidirectional"))
    )
    (net (code "102") (name "Net-(IC4A-C2-)") (class "Default")
      (node (ref "C9") (pin "2") (pinfunction "2_2") (pintype "passive"))
      (node (ref "IC4") (pin "5") (pinfunction "C2-_5") (pintype "bidirectional"))
    )
    (net (code "103") (name "Net-(IC4A-V+)") (class "Default")
      (node (ref "C7") (pin "1") (pinfunction "1_1") (pintype "passive"))
      (node (ref "IC4") (pin "2") (pinfunction "V+_2") (pintype "bidirectional"))
    )
    (net (code "104") (name "Net-(IC4A-V-)") (class "Default")
      (node (ref "C8") (pin "2") (pinfunction "2_2") (pintype "passive"))
      (node (ref "IC4") (pin "6") (pinfunction "V-_6") (pintype "bidirectional"))
    )
    (net (code "105") (name "Net-(JP3-Pad6)") (class "Default")
      (node (ref "JP3") (pin "6") (pinfunction "6_6") (pintype "passive"))
      (node (ref "JP4") (pin "3") (pinfunction "3_3") (pintype "passive"))
    )
    (net (code "106") (name "Net-(JP4-Pad4)") (class "Default")
      (node (ref "JP4") (pin "4") (pinfunction "4_4") (pintype "passive"))
      (node (ref "JP5") (pin "2") (pinfunction "2_2") (pintype "passive"))
    )
    (net (code "107") (name "Net-(JP5-Pad1)") (class "Default")
      (node (ref "JP5") (pin "1") (pinfunction "1_1") (pintype "passive"))
      (node (ref "JP6") (pin "2") (pinfunction "2_2") (pintype "passive"))
    )
    (net (code "108") (name "Net-(L2-Pad2)") (class "Default")
      (node (ref "L2") (pin "2") (pinfunction "2_2") (pintype "passive"))
      (node (ref "R19") (pin "1") (pinfunction "1_1") (pintype "passive"))
      (node (ref "R23") (pin "2") (pinfunction "2_2") (pintype "passive"))
    )
    (net (code "109") (name "Net-(L3-Pad2)") (class "Default")
      (node (ref "L3") (pin "2") (pinfunction "2_2") (pintype "passive"))
      (node (ref "R20") (pin "1") (pinfunction "1_1") (pintype "passive"))
      (node (ref "R24") (pin "2") (pinfunction "2_2") (pintype "passive"))
    )
    (net (code "110") (name "Net-(L4-Pad2)") (class "Default")
      (node (ref "L4") (pin "2") (pinfunction "2_2") (pintype "passive"))
      (node (ref "R21") (pin "1") (pinfunction "1_1") (pintype "passive"))
      (node (ref "R25") (pin "2") (pinfunction "2_2") (pintype "passive"))
    )
    (net (code "111") (name "Net-(L5-Pad2)") (class "Default")
      (node (ref "L5") (pin "2") (pinfunction "2_2") (pintype "passive"))
      (node (ref "R37") (pin "1") (pinfunction "1_1") (pintype "passive"))
      (node (ref "R40") (pin "2") (pinfunction "2_2") (pintype "passive"))
    )
    (net (code "112") (name "Net-(L6-Pad2)") (class "Default")
      (node (ref "L6") (pin "2") (pinfunction "2_2") (pintype "passive"))
      (node (ref "R38") (pin "1") (pinfunction "1_1") (pintype "passive"))
      (node (ref "R41") (pin "2") (pinfunction "2_2") (pintype "passive"))
    )
    (net (code "113") (name "Net-(L7-Pad2)") (class "Default")
      (node (ref "L7") (pin "2") (pinfunction "2_2") (pintype "passive"))
      (node (ref "R39") (pin "1") (pinfunction "1_1") (pintype "passive"))
      (node (ref "R42") (pin "2") (pinfunction "2_2") (pintype "passive"))
    )
    (net (code "114") (name "Net-(LED1-PadA)") (class "Default")
      (node (ref "LED1") (pin "A") (pinfunction "A_A") (pintype "passive"))
      (node (ref "R18") (pin "2") (pinfunction "2_2") (pintype "passive"))
    )
    (net (code "115") (name "Net-(R52-Pad2)") (class "Default")
      (node (ref "R52") (pin "2") (pinfunction "2_2") (pintype "passive"))
      (node (ref "SJ1") (pin "1") (pinfunction "1_1") (pintype "passive"))
    )
    (net (code "116") (name "Net-(R53-Pad2)") (class "Default")
      (node (ref "R53") (pin "2") (pinfunction "2_2") (pintype "passive"))
      (node (ref "SJ2") (pin "1") (pinfunction "1_1") (pintype "passive"))
    )
    (net (code "117") (name "Net-(X1--1)") (class "Default")
      (node (ref "F1") (pin "1") (pinfunction "1_1") (pintype "passive"))
      (node (ref "X1") (pin "A1") (pinfunction "-1_A1") (pintype "passive"))
    )
    (net (code "118") (name "unconnected-(IC2A-ST1{slash}2-Pad4)") (class "Default")
      (node (ref "IC2") (pin "4") (pinfunction "ST1/2_4") (pintype "input"))
    )
    (net (code "119") (name "unconnected-(IC2A-ST3{slash}4-Pad8)") (class "Default")
      (node (ref "IC2") (pin "8") (pinfunction "ST3/4_8") (pintype "input"))
    )
    (net (code "120") (name "unconnected-(IC3A-ST1{slash}2-Pad4)") (class "Default")
      (node (ref "IC3") (pin "4") (pinfunction "ST1/2_4") (pintype "input"))
    )
    (net (code "121") (name "unconnected-(IC3A-ST3{slash}4-Pad8)") (class "Default")
      (node (ref "IC3") (pin "8") (pinfunction "ST3/4_8") (pintype "input"))
    )
    (net (code "122") (name "unconnected-(IC4A-R2OUT-Pad9)") (class "Default")
      (node (ref "IC4") (pin "9") (pinfunction "R2OUT_9") (pintype "output"))
    )
    (net (code "123") (name "unconnected-(IC4A-T2OUT-Pad7)") (class "Default")
      (node (ref "IC4") (pin "7") (pinfunction "T2OUT_7") (pintype "output"))
    )
    (net (code "124") (name "unconnected-(OLIMEXINO-STM1-Pad3V3)") (class "Default")
      (node (ref "OLIMEXINO-STM1") (pin "3V3") (pinfunction "3V3_3V3") (pintype "bidirectional"))
    )
    (net (code "125") (name "unconnected-(OLIMEXINO-STM1-PadA1)") (class "Default")
      (node (ref "OLIMEXINO-STM1") (pin "A1") (pinfunction "A1_A1") (pintype "bidirectional"))
    )
    (net (code "126") (name "unconnected-(OLIMEXINO-STM1-RESET-PadRST)") (class "Default")
      (node (ref "OLIMEXINO-STM1") (pin "RST") (pinfunction "RESET_RST") (pintype "bidirectional"))
    )
    (net (code "127") (name "unconnected-(X1-B-1-PadB1)") (class "Default")
      (node (ref "X1") (pin "B1") (pinfunction "B-1_B1") (pintype "passive"))
    )
    (net (code "128") (name "unconnected-(X1-B-2-PadB2)") (class "Default")
      (node (ref "X1") (pin "B2") (pinfunction "B-2_B2") (pintype "passive"))
    )
  )
)
